# schematic.net
KiCad netlist of a schematic drawn in EAGLE
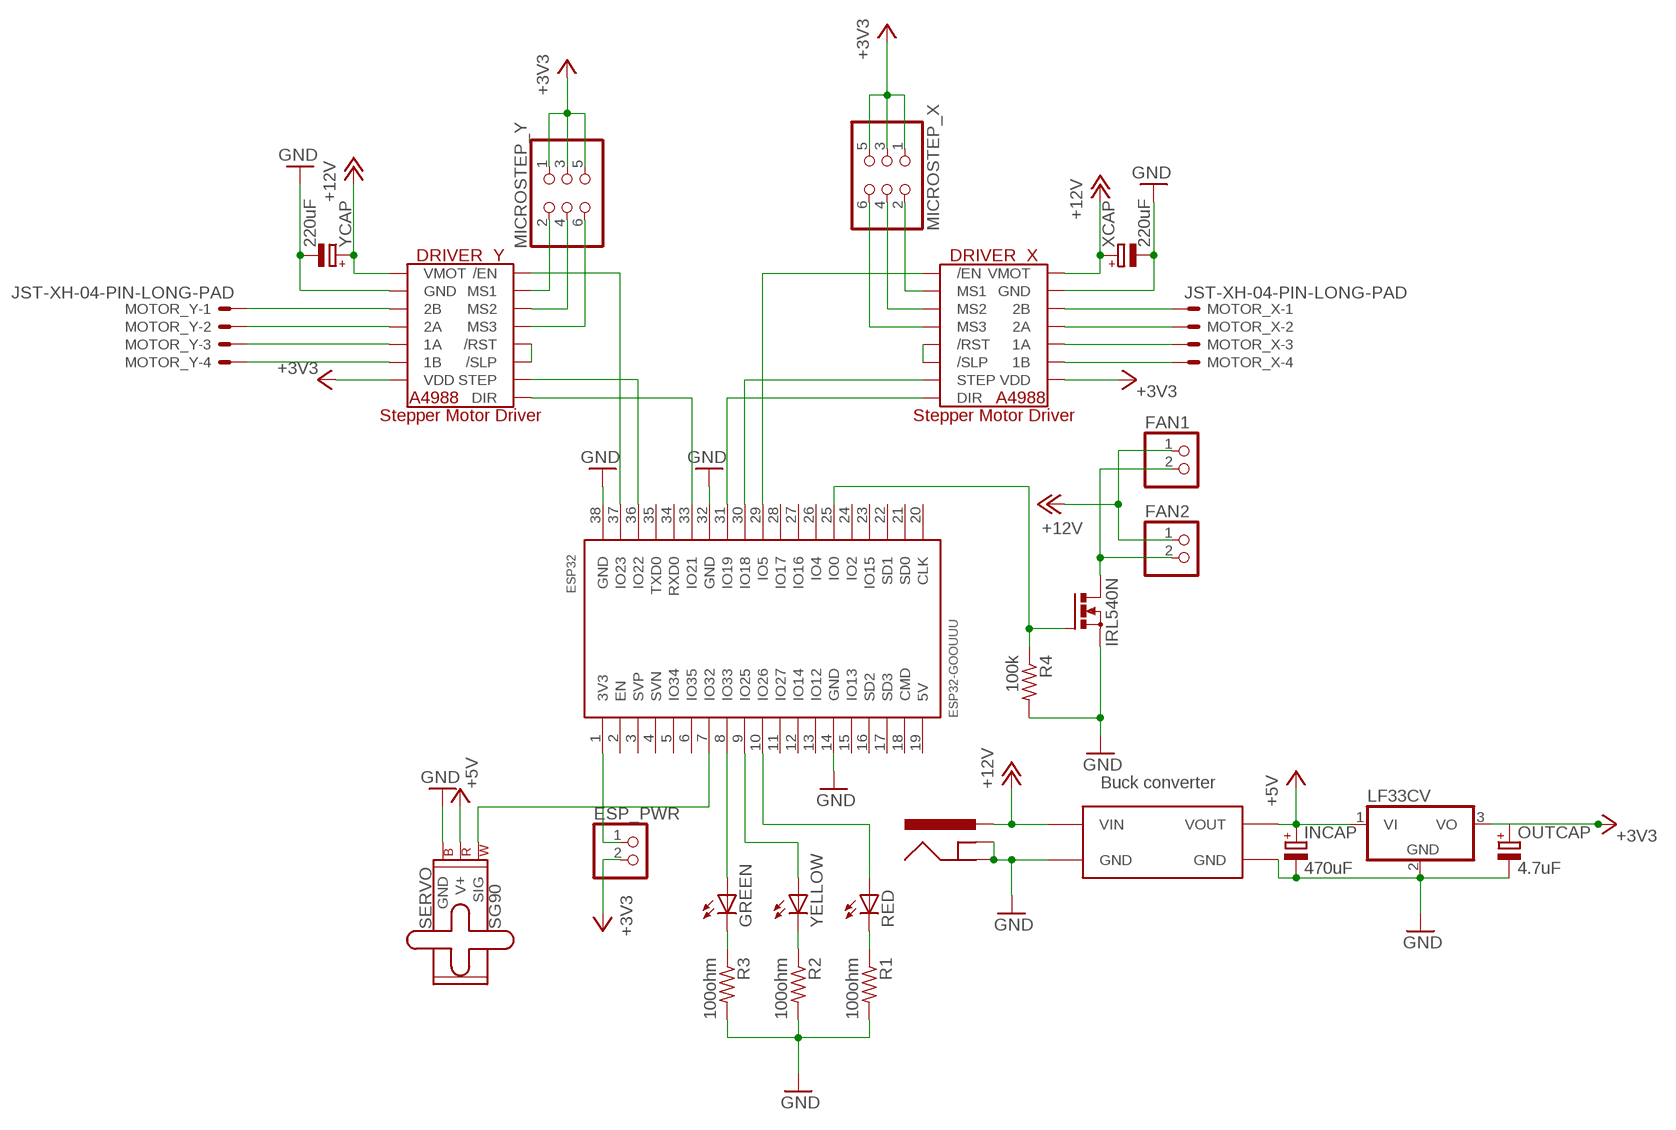
[diagram p0: schematic, sheet 1]

(export (version "E")
  (design (tool "Eeschema 10.0.6"))
  (components
    (comp (ref "DRIVER_X")
      (value "A4988_STEP")
      (footprint "eagle-import:A4988_STEP")
      (libsource (lib "eagle-import") (part "A4988_STEP"))
    )
    (comp (ref "DRIVER_Y")
      (value "A4988_STEP")
      (footprint "eagle-import:A4988_STEP")
      (libsource (lib "eagle-import") (part "A4988_STEP"))
    )
    (comp (ref "ESP32")
      (value "ESP32-GOOUUU")
      (footprint "eagle-import:ESP32--GOOUUU")
      (libsource (lib "eagle-import") (part "ESP32-GOOUUU"))
    )
    (comp (ref "ESP_PWR")
      (value "PINHD-1X2")
      (footprint "eagle-import:1X02")
      (libsource (lib "eagle-import") (part "PINHD-1X2"))
    )
    (comp (ref "FAN1")
      (value "PINHD-1X2")
      (footprint "eagle-import:1X02")
      (libsource (lib "eagle-import") (part "PINHD-1X2"))
    )
    (comp (ref "FAN2")
      (value "PINHD-1X2")
      (footprint "eagle-import:1X02")
      (libsource (lib "eagle-import") (part "PINHD-1X2"))
    )
    (comp (ref "GREEN")
      (value "LED5MM")
      (footprint "eagle-import:LED5MM")
      (libsource (lib "eagle-import") (part "LED5MM"))
    )
    (comp (ref "INCAP")
      (value "470uF")
      (footprint "eagle-import:E2,5RE")
      (libsource (lib "eagle-import") (part "CPOL-EUE2.5-4V"))
    )
    (comp (ref "IRL540N")
      (value "PMOSFET_NTO220BV")
      (footprint "eagle-import:TO220BV")
      (libsource (lib "eagle-import") (part "PMOSFET_NTO220BV"))
    )
    (comp (ref "LF33CV")
      (value "LF33CVTV")
      (footprint "eagle-import:TO220V")
      (libsource (lib "eagle-import") (part "LF33CVTV"))
    )
    (comp (ref "MICROSTEP_X")
      (value "PINHD-2X3")
      (footprint "eagle-import:2X03")
      (libsource (lib "eagle-import") (part "PINHD-2X3"))
    )
    (comp (ref "MICROSTEP_Y")
      (value "PINHD-2X3")
      (footprint "eagle-import:2X03")
      (libsource (lib "eagle-import") (part "PINHD-2X3"))
    )
    (comp (ref "MOTOR_X")
      (value "JST-XH-04-PIN-LONG-PAD")
      (footprint "eagle-import:JST-XH-04-PACKAGE-LONG-PAD")
      (libsource (lib "eagle-import") (part "JST-XH-04-PIN-LONG-PAD"))
    )
    (comp (ref "MOTOR_Y")
      (value "JST-XH-04-PIN-LONG-PAD")
      (footprint "eagle-import:JST-XH-04-PACKAGE-LONG-PAD")
      (libsource (lib "eagle-import") (part "JST-XH-04-PIN-LONG-PAD"))
    )
    (comp (ref "OUTCAP")
      (value "4.7uF")
      (footprint "eagle-import:E2,5RE")
      (libsource (lib "eagle-import") (part "CPOL-EUE2.5-4V"))
    )
    (comp (ref "POWER_JACK")
      (value "POWER_JACKPTH")
      (footprint "eagle-import:POWER_JACK_PTH")
      (libsource (lib "eagle-import") (part "POWER_JACKPTH"))
    )
    (comp (ref "R1")
      (value "100ohm")
      (footprint "eagle-import:0207_10")
      (libsource (lib "eagle-import") (part "R-US_0207/10"))
    )
    (comp (ref "R2")
      (value "100ohm")
      (footprint "eagle-import:0207_10")
      (libsource (lib "eagle-import") (part "R-US_0207/10"))
    )
    (comp (ref "R3")
      (value "100ohm")
      (footprint "eagle-import:0207_10")
      (libsource (lib "eagle-import") (part "R-US_0207/10"))
    )
    (comp (ref "R4")
      (value "100k")
      (footprint "eagle-import:0207_10")
      (libsource (lib "eagle-import") (part "R-US_0207/10"))
    )
    (comp (ref "RED")
      (value "LED5MM")
      (footprint "eagle-import:LED5MM")
      (libsource (lib "eagle-import") (part "LED5MM"))
    )
    (comp (ref "SG90")
      (value "SERVO")
      (footprint "eagle-import:1X03")
      (libsource (lib "eagle-import") (part "SERVO"))
    )
    (comp (ref "U$2")
      (value "BUCK-CONVERTER")
      (footprint "eagle-import:BUCK-CONVERTER")
      (libsource (lib "eagle-import") (part "BUCK-CONVERTER"))
    )
    (comp (ref "XCAP")
      (value "220uF")
      (footprint "eagle-import:E2,5-6")
      (libsource (lib "eagle-import") (part "CPOL-EUE2.5-6"))
    )
    (comp (ref "YCAP")
      (value "220uF")
      (footprint "eagle-import:E2,5-6")
      (libsource (lib "eagle-import") (part "CPOL-EUE2.5-6"))
    )
    (comp (ref "YELLOW")
      (value "LED5MM")
      (footprint "eagle-import:LED5MM")
      (libsource (lib "eagle-import") (part "LED5MM"))
    )
  )
  (nets
    (net (code "1") (name "+3V3") (class "Default")
      (node (ref "DRIVER_X") (pin "VDD") (pinfunction "VDD_VDD") (pintype "bidirectional"))
      (node (ref "DRIVER_Y") (pin "VDD") (pinfunction "VDD_VDD") (pintype "bidirectional"))
      (node (ref "ESP_PWR") (pin "2") (pinfunction "2_2") (pintype "passive"))
      (node (ref "LF33CV") (pin "3") (pinfunction "VO_3") (pintype "passive"))
      (node (ref "MICROSTEP_X") (pin "1") (pinfunction "1_1") (pintype "passive"))
      (node (ref "MICROSTEP_X") (pin "3") (pinfunction "3_3") (pintype "passive"))
      (node (ref "MICROSTEP_X") (pin "5") (pinfunction "5_5") (pintype "passive"))
      (node (ref "MICROSTEP_Y") (pin "1") (pinfunction "1_1") (pintype "passive"))
      (node (ref "MICROSTEP_Y") (pin "3") (pinfunction "3_3") (pintype "passive"))
      (node (ref "MICROSTEP_Y") (pin "5") (pinfunction "5_5") (pintype "passive"))
      (node (ref "OUTCAP") (pin "+") (pinfunction "+_+") (pintype "passive"))
    )
    (net (code "2") (name "+5V") (class "Default")
      (node (ref "INCAP") (pin "+") (pinfunction "+_+") (pintype "passive"))
      (node (ref "LF33CV") (pin "1") (pinfunction "VI_1") (pintype "input"))
      (node (ref "SG90") (pin "2") (pinfunction "V+_2") (pintype "bidirectional"))
      (node (ref "U$2") (pin "VOUT1") (pinfunction "VOUT_VOUT1") (pintype "bidirectional"))
      (node (ref "U$2") (pin "VOUT2") (pinfunction "VOUT_VOUT2") (pintype "bidirectional"))
    )
    (net (code "3") (name "+12V") (class "Default")
      (node (ref "DRIVER_X") (pin "VMOT") (pinfunction "VMOT_VMOT") (pintype "bidirectional"))
      (node (ref "DRIVER_Y") (pin "VMOT") (pinfunction "VMOT_VMOT") (pintype "bidirectional"))
      (node (ref "FAN1") (pin "1") (pinfunction "1_1") (pintype "passive"))
      (node (ref "FAN2") (pin "1") (pinfunction "1_1") (pintype "passive"))
      (node (ref "POWER_JACK") (pin "PWR") (pinfunction "PWR_PWR") (pintype "bidirectional"))
      (node (ref "U$2") (pin "VIN1") (pinfunction "VIN_VIN1") (pintype "bidirectional"))
      (node (ref "U$2") (pin "VIN2") (pinfunction "VIN_VIN2") (pintype "bidirectional"))
      (node (ref "XCAP") (pin "+") (pinfunction "+_+") (pintype "passive"))
      (node (ref "YCAP") (pin "+") (pinfunction "+_+") (pintype "passive"))
    )
    (net (code "4") (name "GND") (class "Default")
      (node (ref "DRIVER_X") (pin "GND") (pinfunction "GND_GND") (pintype "bidirectional"))
      (node (ref "DRIVER_X") (pin "GND2") (pinfunction "GND_GND2") (pintype "bidirectional"))
      (node (ref "DRIVER_Y") (pin "GND") (pinfunction "GND_GND") (pintype "bidirectional"))
      (node (ref "DRIVER_Y") (pin "GND2") (pinfunction "GND_GND2") (pintype "bidirectional"))
      (node (ref "ESP32") (pin "14") (pinfunction "GND_14") (pintype "bidirectional"))
      (node (ref "ESP32") (pin "32") (pinfunction "GND_32") (pintype "bidirectional"))
      (node (ref "ESP32") (pin "38") (pinfunction "GND_38") (pintype "bidirectional"))
      (node (ref "INCAP") (pin "-") (pinfunction "-_-") (pintype "passive"))
      (node (ref "IRL540N") (pin "S") (pinfunction "S_S") (pintype "passive"))
      (node (ref "LF33CV") (pin "2") (pinfunction "GND_2") (pintype "passive"))
      (node (ref "OUTCAP") (pin "-") (pinfunction "-_-") (pintype "passive"))
      (node (ref "POWER_JACK") (pin "GND") (pinfunction "GND_GND") (pintype "bidirectional"))
      (node (ref "POWER_JACK") (pin "GND@1") (pinfunction "GND_GND@1") (pintype "bidirectional"))
      (node (ref "R1") (pin "2") (pinfunction "2_2") (pintype "passive"))
      (node (ref "R2") (pin "2") (pinfunction "2_2") (pintype "passive"))
      (node (ref "R3") (pin "2") (pinfunction "2_2") (pintype "passive"))
      (node (ref "R4") (pin "2") (pinfunction "2_2") (pintype "passive"))
      (node (ref "SG90") (pin "3") (pinfunction "GND_3") (pintype "bidirectional"))
      (node (ref "U$2") (pin "GND@1") (pinfunction "GND_GND@1") (pintype "bidirectional"))
      (node (ref "U$2") (pin "GND@2") (pinfunction "GND_GND@2") (pintype "bidirectional"))
      (node (ref "U$2") (pin "GND@3") (pinfunction "GND_GND@3") (pintype "bidirectional"))
      (node (ref "U$2") (pin "GND@4") (pinfunction "GND_GND@4") (pintype "bidirectional"))
      (node (ref "XCAP") (pin "-") (pinfunction "-_-") (pintype "passive"))
      (node (ref "YCAP") (pin "-") (pinfunction "-_-") (pintype "passive"))
    )
    (net (code "5") (name "Net-(DRIVER_X-PadMS1)") (class "Default")
      (node (ref "DRIVER_X") (pin "MS1") (pinfunction "MS1_MS1") (pintype "bidirectional"))
      (node (ref "MICROSTEP_X") (pin "2") (pinfunction "2_2") (pintype "passive"))
    )
    (net (code "6") (name "Net-(DRIVER_X-PadMS2)") (class "Default")
      (node (ref "DRIVER_X") (pin "MS2") (pinfunction "MS2_MS2") (pintype "bidirectional"))
      (node (ref "MICROSTEP_X") (pin "4") (pinfunction "4_4") (pintype "passive"))
    )
    (net (code "7") (name "Net-(DRIVER_X-PadMS3)") (class "Default")
      (node (ref "DRIVER_X") (pin "MS3") (pinfunction "MS3_MS3") (pintype "bidirectional"))
      (node (ref "MICROSTEP_X") (pin "6") (pinfunction "6_6") (pintype "passive"))
    )
    (net (code "8") (name "Net-(DRIVER_X-Pad{slash}RST)") (class "Default")
      (node (ref "DRIVER_X") (pin "/RST") (pinfunction "/RST_/RST") (pintype "bidirectional"))
      (node (ref "DRIVER_X") (pin "/SLP") (pinfunction "/SLP_/SLP") (pintype "bidirectional"))
    )
    (net (code "9") (name "Net-(DRIVER_Y-PadMS1)") (class "Default")
      (node (ref "DRIVER_Y") (pin "MS1") (pinfunction "MS1_MS1") (pintype "bidirectional"))
      (node (ref "MICROSTEP_Y") (pin "2") (pinfunction "2_2") (pintype "passive"))
    )
    (net (code "10") (name "Net-(DRIVER_Y-PadMS2)") (class "Default")
      (node (ref "DRIVER_Y") (pin "MS2") (pinfunction "MS2_MS2") (pintype "bidirectional"))
      (node (ref "MICROSTEP_Y") (pin "4") (pinfunction "4_4") (pintype "passive"))
    )
    (net (code "11") (name "Net-(DRIVER_Y-PadMS3)") (class "Default")
      (node (ref "DRIVER_Y") (pin "MS3") (pinfunction "MS3_MS3") (pintype "bidirectional"))
      (node (ref "MICROSTEP_Y") (pin "6") (pinfunction "6_6") (pintype "passive"))
    )
    (net (code "12") (name "Net-(DRIVER_Y-Pad{slash}RST)") (class "Default")
      (node (ref "DRIVER_Y") (pin "/RST") (pinfunction "/RST_/RST") (pintype "bidirectional"))
      (node (ref "DRIVER_Y") (pin "/SLP") (pinfunction "/SLP_/SLP") (pintype "bidirectional"))
    )
    (net (code "13") (name "Net-(ESP32-3V3)") (class "Default")
      (node (ref "ESP32") (pin "1") (pinfunction "3V3_1") (pintype "bidirectional"))
      (node (ref "ESP_PWR") (pin "1") (pinfunction "1_1") (pintype "passive"))
    )
    (net (code "14") (name "Net-(ESP32-IO0)") (class "Default")
      (node (ref "ESP32") (pin "25") (pinfunction "IO0_25") (pintype "bidirectional"))
      (node (ref "IRL540N") (pin "G") (pinfunction "G_G") (pintype "passive"))
      (node (ref "R4") (pin "1") (pinfunction "1_1") (pintype "passive"))
    )
    (net (code "15") (name "Net-(ESP32-IO5)") (class "Default")
      (node (ref "DRIVER_X") (pin "/EN") (pinfunction "/EN_/EN") (pintype "bidirectional"))
      (node (ref "ESP32") (pin "29") (pinfunction "IO5_29") (pintype "bidirectional"))
    )
    (net (code "16") (name "Net-(ESP32-IO18)") (class "Default")
      (node (ref "DRIVER_X") (pin "STEP") (pinfunction "STEP_STEP") (pintype "bidirectional"))
      (node (ref "ESP32") (pin "30") (pinfunction "IO18_30") (pintype "bidirectional"))
    )
    (net (code "17") (name "Net-(ESP32-IO19)") (class "Default")
      (node (ref "DRIVER_X") (pin "DIR") (pinfunction "DIR_DIR") (pintype "bidirectional"))
      (node (ref "ESP32") (pin "31") (pinfunction "IO19_31") (pintype "bidirectional"))
    )
    (net (code "18") (name "Net-(ESP32-IO21)") (class "Default")
      (node (ref "DRIVER_Y") (pin "DIR") (pinfunction "DIR_DIR") (pintype "bidirectional"))
      (node (ref "ESP32") (pin "33") (pinfunction "IO21_33") (pintype "bidirectional"))
    )
    (net (code "19") (name "Net-(ESP32-IO22)") (class "Default")
      (node (ref "DRIVER_Y") (pin "STEP") (pinfunction "STEP_STEP") (pintype "bidirectional"))
      (node (ref "ESP32") (pin "36") (pinfunction "IO22_36") (pintype "bidirectional"))
    )
    (net (code "20") (name "Net-(ESP32-IO23)") (class "Default")
      (node (ref "DRIVER_Y") (pin "/EN") (pinfunction "/EN_/EN") (pintype "bidirectional"))
      (node (ref "ESP32") (pin "37") (pinfunction "IO23_37") (pintype "bidirectional"))
    )
    (net (code "21") (name "Net-(ESP32-IO25)") (class "Default")
      (node (ref "ESP32") (pin "9") (pinfunction "IO25_9") (pintype "bidirectional"))
      (node (ref "YELLOW") (pin "A") (pinfunction "A_A") (pintype "passive"))
    )
    (net (code "22") (name "Net-(ESP32-IO26)") (class "Default")
      (node (ref "ESP32") (pin "10") (pinfunction "IO26_10") (pintype "bidirectional"))
      (node (ref "RED") (pin "A") (pinfunction "A_A") (pintype "passive"))
    )
    (net (code "23") (name "Net-(ESP32-IO32)") (class "Default")
      (node (ref "ESP32") (pin "7") (pinfunction "IO32_7") (pintype "bidirectional"))
      (node (ref "SG90") (pin "1") (pinfunction "SIG_1") (pintype "bidirectional"))
    )
    (net (code "24") (name "Net-(ESP32-IO33)") (class "Default")
      (node (ref "ESP32") (pin "8") (pinfunction "IO33_8") (pintype "bidirectional"))
      (node (ref "GREEN") (pin "A") (pinfunction "A_A") (pintype "passive"))
    )
    (net (code "25") (name "Net-(FAN1-Pad2)") (class "Default")
      (node (ref "FAN1") (pin "2") (pinfunction "2_2") (pintype "passive"))
      (node (ref "FAN2") (pin "2") (pinfunction "2_2") (pintype "passive"))
      (node (ref "IRL540N") (pin "D") (pinfunction "D_D") (pintype "passive"))
    )
    (net (code "26") (name "Net-(GREEN-C)") (class "Default")
      (node (ref "GREEN") (pin "K") (pinfunction "C_K") (pintype "passive"))
      (node (ref "R3") (pin "1") (pinfunction "1_1") (pintype "passive"))
    )
    (net (code "27") (name "Net-(MOTOR_XA-S)") (class "Default")
      (node (ref "DRIVER_X") (pin "2B") (pinfunction "2B_2B") (pintype "bidirectional"))
      (node (ref "MOTOR_X") (pin "1") (pinfunction "S_1") (pintype "passive"))
    )
    (net (code "28") (name "Net-(MOTOR_XB-S)") (class "Default")
      (node (ref "DRIVER_X") (pin "2A") (pinfunction "2A_2A") (pintype "bidirectional"))
      (node (ref "MOTOR_X") (pin "2") (pinfunction "S_2") (pintype "passive"))
    )
    (net (code "29") (name "Net-(MOTOR_XC-S)") (class "Default")
      (node (ref "DRIVER_X") (pin "1A") (pinfunction "1A_1A") (pintype "bidirectional"))
      (node (ref "MOTOR_X") (pin "3") (pinfunction "S_3") (pintype "passive"))
    )
    (net (code "30") (name "Net-(MOTOR_XD-S)") (class "Default")
      (node (ref "DRIVER_X") (pin "1B") (pinfunction "1B_1B") (pintype "bidirectional"))
      (node (ref "MOTOR_X") (pin "4") (pinfunction "S_4") (pintype "passive"))
    )
    (net (code "31") (name "Net-(MOTOR_YA-S)") (class "Default")
      (node (ref "DRIVER_Y") (pin "2B") (pinfunction "2B_2B") (pintype "bidirectional"))
      (node (ref "MOTOR_Y") (pin "1") (pinfunction "S_1") (pintype "passive"))
    )
    (net (code "32") (name "Net-(MOTOR_YB-S)") (class "Default")
      (node (ref "DRIVER_Y") (pin "2A") (pinfunction "2A_2A") (pintype "bidirectional"))
      (node (ref "MOTOR_Y") (pin "2") (pinfunction "S_2") (pintype "passive"))
    )
    (net (code "33") (name "Net-(MOTOR_YC-S)") (class "Default")
      (node (ref "DRIVER_Y") (pin "1A") (pinfunction "1A_1A") (pintype "bidirectional"))
      (node (ref "MOTOR_Y") (pin "3") (pinfunction "S_3") (pintype "passive"))
    )
    (net (code "34") (name "Net-(MOTOR_YD-S)") (class "Default")
      (node (ref "DRIVER_Y") (pin "1B") (pinfunction "1B_1B") (pintype "bidirectional"))
      (node (ref "MOTOR_Y") (pin "4") (pinfunction "S_4") (pintype "passive"))
    )
    (net (code "35") (name "Net-(RED-C)") (class "Default")
      (node (ref "R1") (pin "1") (pinfunction "1_1") (pintype "passive"))
      (node (ref "RED") (pin "K") (pinfunction "C_K") (pintype "passive"))
    )
    (net (code "36") (name "Net-(YELLOW-C)") (class "Default")
      (node (ref "R2") (pin "1") (pinfunction "1_1") (pintype "passive"))
      (node (ref "YELLOW") (pin "K") (pinfunction "C_K") (pintype "passive"))
    )
    (net (code "37") (name "unconnected-(ESP32-5V-Pad19)") (class "Default")
      (node (ref "ESP32") (pin "19") (pinfunction "5V_19") (pintype "bidirectional"))
    )
    (net (code "38") (name "unconnected-(ESP32-CLK-Pad20)") (class "Default")
      (node (ref "ESP32") (pin "20") (pinfunction "CLK_20") (pintype "bidirectional"))
    )
    (net (code "39") (name "unconnected-(ESP32-CMD-Pad18)") (class "Default")
      (node (ref "ESP32") (pin "18") (pinfunction "CMD_18") (pintype "bidirectional"))
    )
    (net (code "40") (name "unconnected-(ESP32-EN-Pad2)") (class "Default")
      (node (ref "ESP32") (pin "2") (pinfunction "EN_2") (pintype "bidirectional"))
    )
    (net (code "41") (name "unconnected-(ESP32-IO2-Pad24)") (class "Default")
      (node (ref "ESP32") (pin "24") (pinfunction "IO2_24") (pintype "bidirectional"))
    )
    (net (code "42") (name "unconnected-(ESP32-IO4-Pad26)") (class "Default")
      (node (ref "ESP32") (pin "26") (pinfunction "IO4_26") (pintype "bidirectional"))
    )
    (net (code "43") (name "unconnected-(ESP32-IO12-Pad13)") (class "Default")
      (node (ref "ESP32") (pin "13") (pinfunction "IO12_13") (pintype "bidirectional"))
    )
    (net (code "44") (name "unconnected-(ESP32-IO13-Pad15)") (class "Default")
      (node (ref "ESP32") (pin "15") (pinfunction "IO13_15") (pintype "bidirectional"))
    )
    (net (code "45") (name "unconnected-(ESP32-IO14-Pad12)") (class "Default")
      (node (ref "ESP32") (pin "12") (pinfunction "IO14_12") (pintype "bidirectional"))
    )
    (net (code "46") (name "unconnected-(ESP32-IO15-Pad23)") (class "Default")
      (node (ref "ESP32") (pin "23") (pinfunction "IO15_23") (pintype "bidirectional"))
    )
    (net (code "47") (name "unconnected-(ESP32-IO16-Pad27)") (class "Default")
      (node (ref "ESP32") (pin "27") (pinfunction "IO16_27") (pintype "bidirectional"))
    )
    (net (code "48") (name "unconnected-(ESP32-IO17-Pad28)") (class "Default")
      (node (ref "ESP32") (pin "28") (pinfunction "IO17_28") (pintype "bidirectional"))
    )
    (net (code "49") (name "unconnected-(ESP32-IO27-Pad11)") (class "Default")
      (node (ref "ESP32") (pin "11") (pinfunction "IO27_11") (pintype "bidirectional"))
    )
    (net (code "50") (name "unconnected-(ESP32-IO34-Pad5)") (class "Default")
      (node (ref "ESP32") (pin "5") (pinfunction "IO34_5") (pintype "bidirectional"))
    )
    (net (code "51") (name "unconnected-(ESP32-IO35-Pad6)") (class "Default")
      (node (ref "ESP32") (pin "6") (pinfunction "IO35_6") (pintype "bidirectional"))
    )
    (net (code "52") (name "unconnected-(ESP32-RXD0-Pad34)") (class "Default")
      (node (ref "ESP32") (pin "34") (pinfunction "RXD0_34") (pintype "bidirectional"))
    )
    (net (code "53") (name "unconnected-(ESP32-SD0-Pad21)") (class "Default")
      (node (ref "ESP32") (pin "21") (pinfunction "SD0_21") (pintype "bidirectional"))
    )
    (net (code "54") (name "unconnected-(ESP32-SD1-Pad22)") (class "Default")
      (node (ref "ESP32") (pin "22") (pinfunction "SD1_22") (pintype "bidirectional"))
    )
    (net (code "55") (name "unconnected-(ESP32-SD2-Pad16)") (class "Default")
      (node (ref "ESP32") (pin "16") (pinfunction "SD2_16") (pintype "bidirectional"))
    )
    (net (code "56") (name "unconnected-(ESP32-SD3-Pad17)") (class "Default")
      (node (ref "ESP32") (pin "17") (pinfunction "SD3_17") (pintype "bidirectional"))
    )
    (net (code "57") (name "unconnected-(ESP32-SVN-Pad4)") (class "Default")
      (node (ref "ESP32") (pin "4") (pinfunction "SVN_4") (pintype "bidirectional"))
    )
    (net (code "58") (name "unconnected-(ESP32-SVP-Pad3)") (class "Default")
      (node (ref "ESP32") (pin "3") (pinfunction "SVP_3") (pintype "bidirectional"))
    )
    (net (code "59") (name "unconnected-(ESP32-TXD0-Pad35)") (class "Default")
      (node (ref "ESP32") (pin "35") (pinfunction "TXD0_35") (pintype "bidirectional"))
    )
  )
)
